# controller_rev3.net
KiCad netlist of a schematic drawn in EAGLE
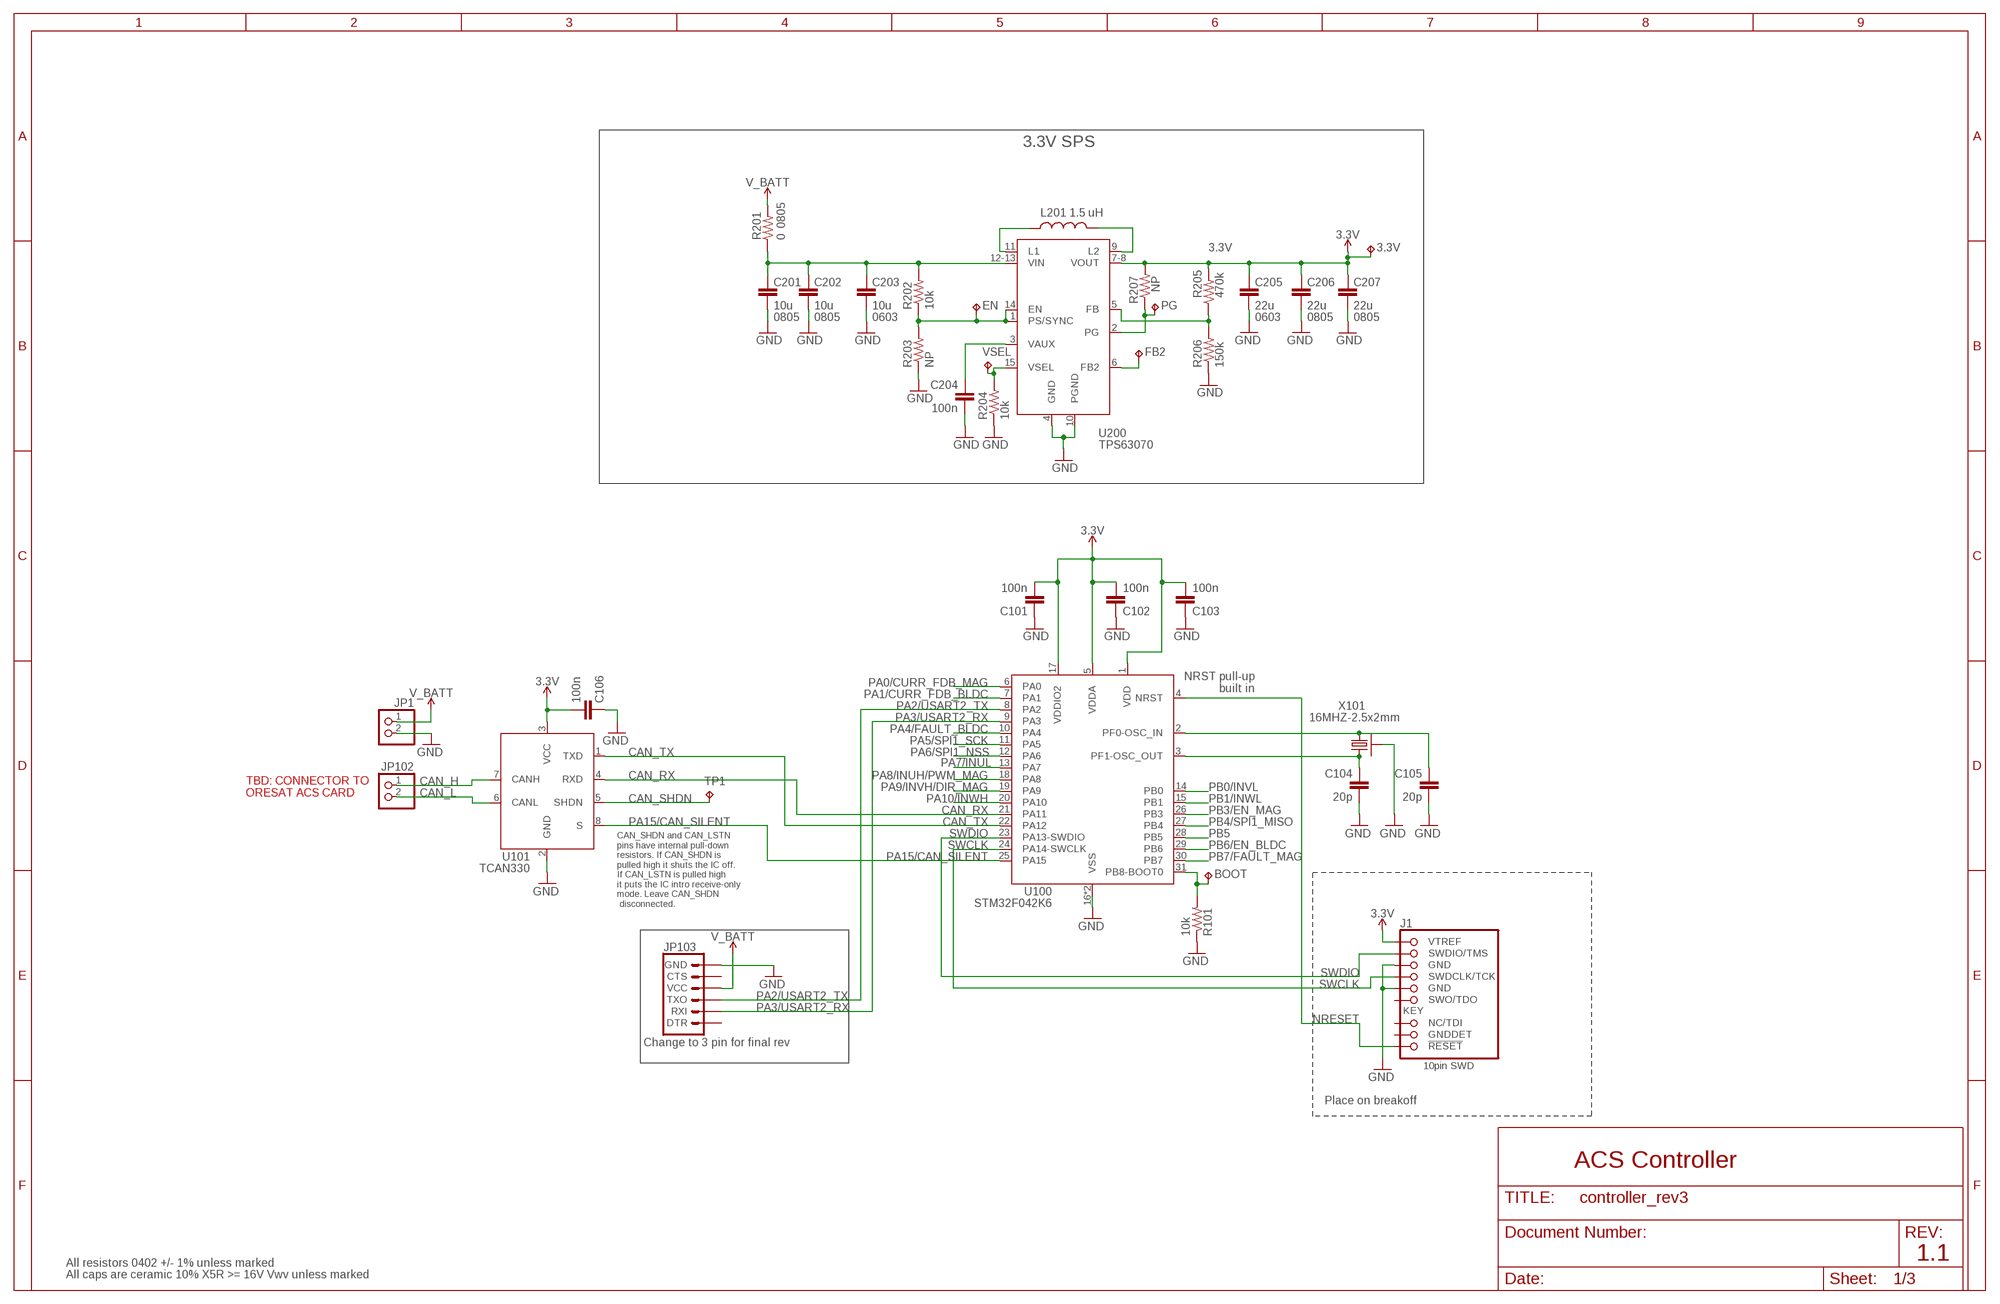
[diagram p0: schematic, sheet 1]
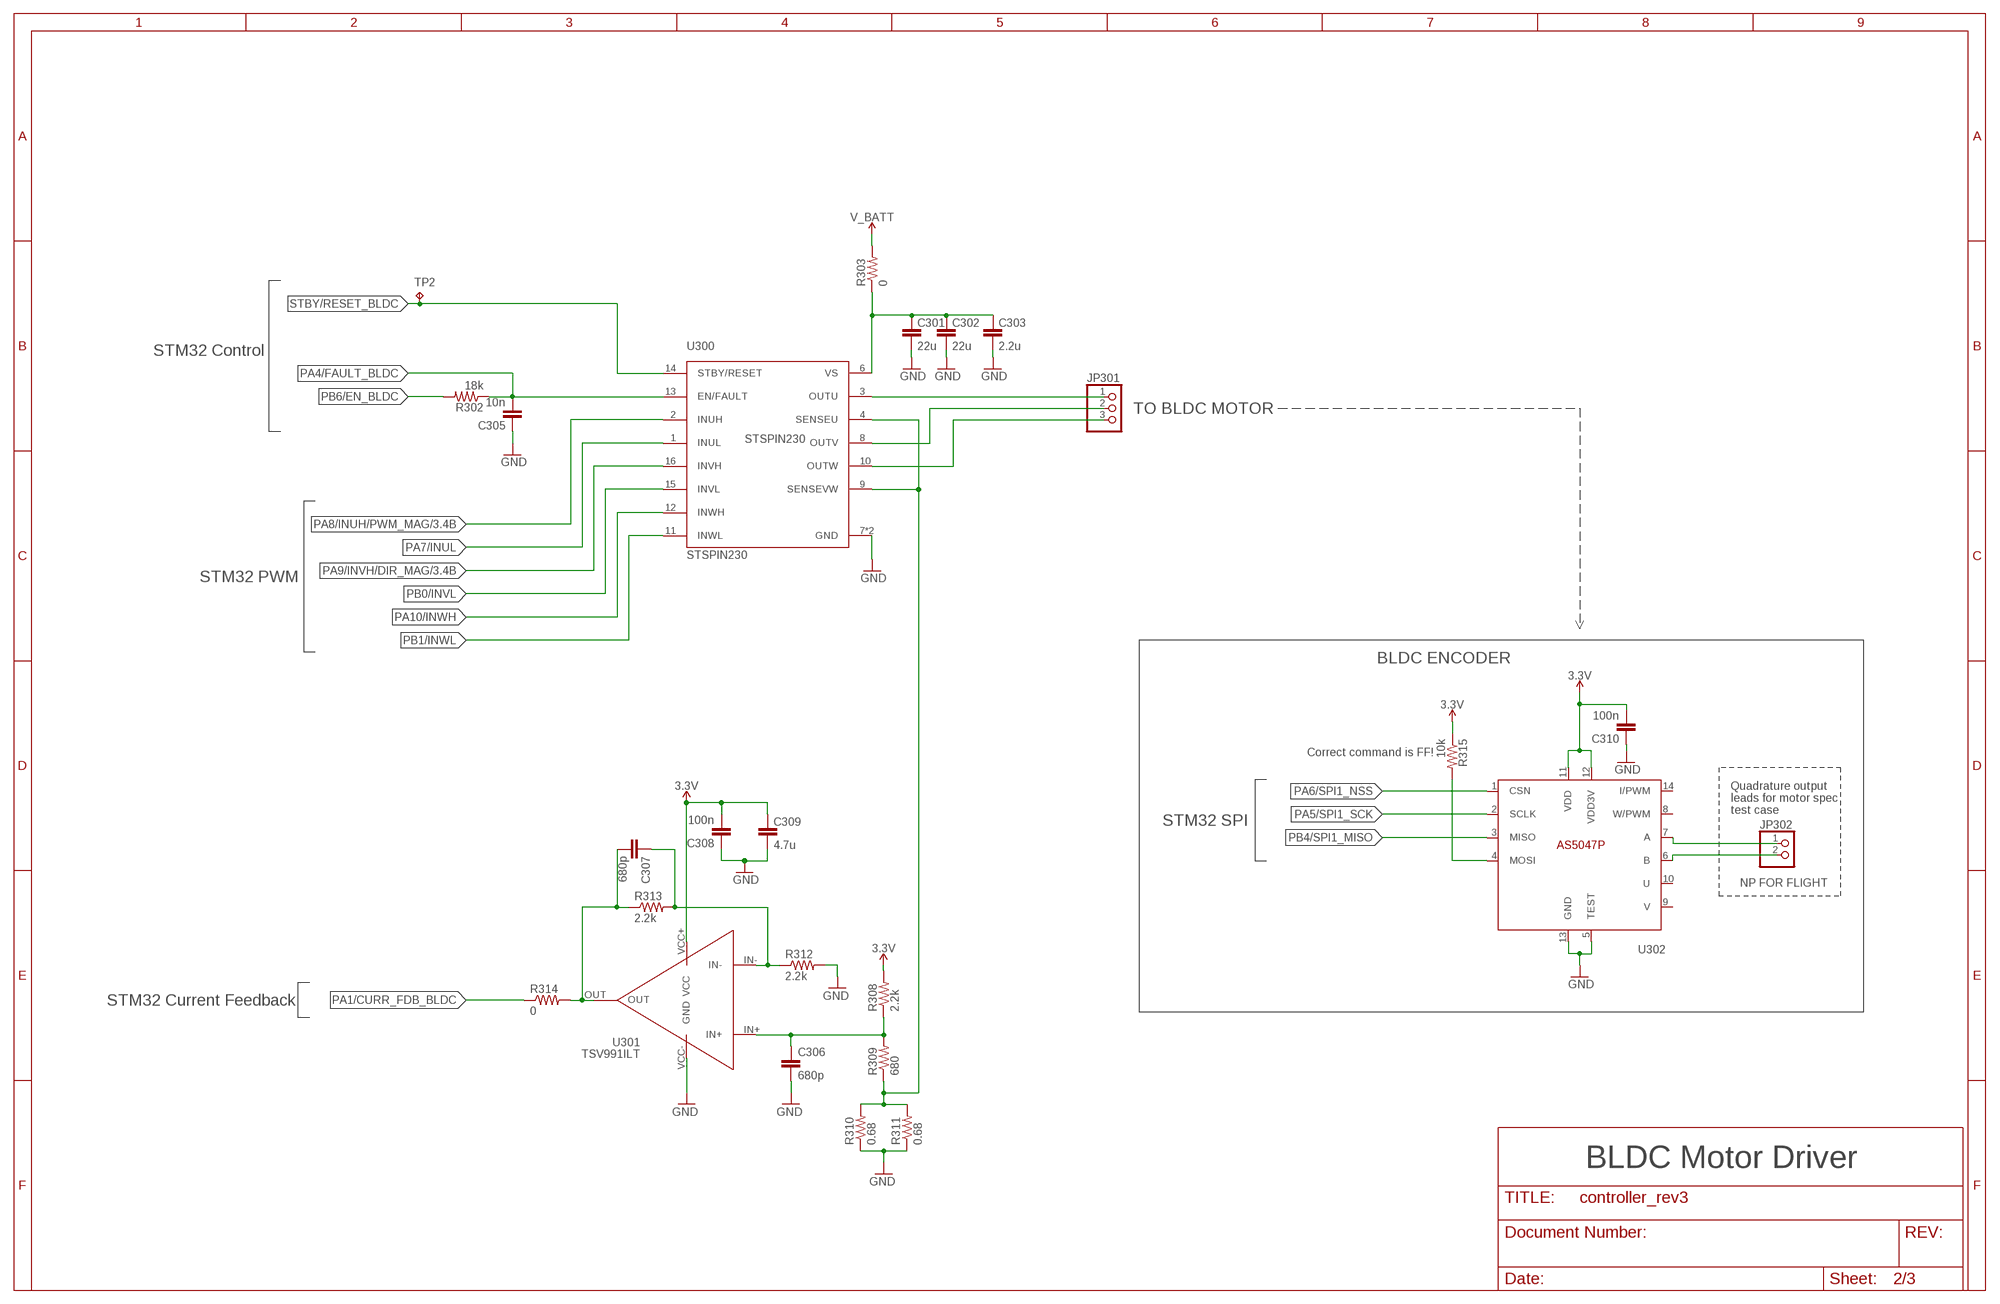
[diagram p1: schematic, sheet 2]
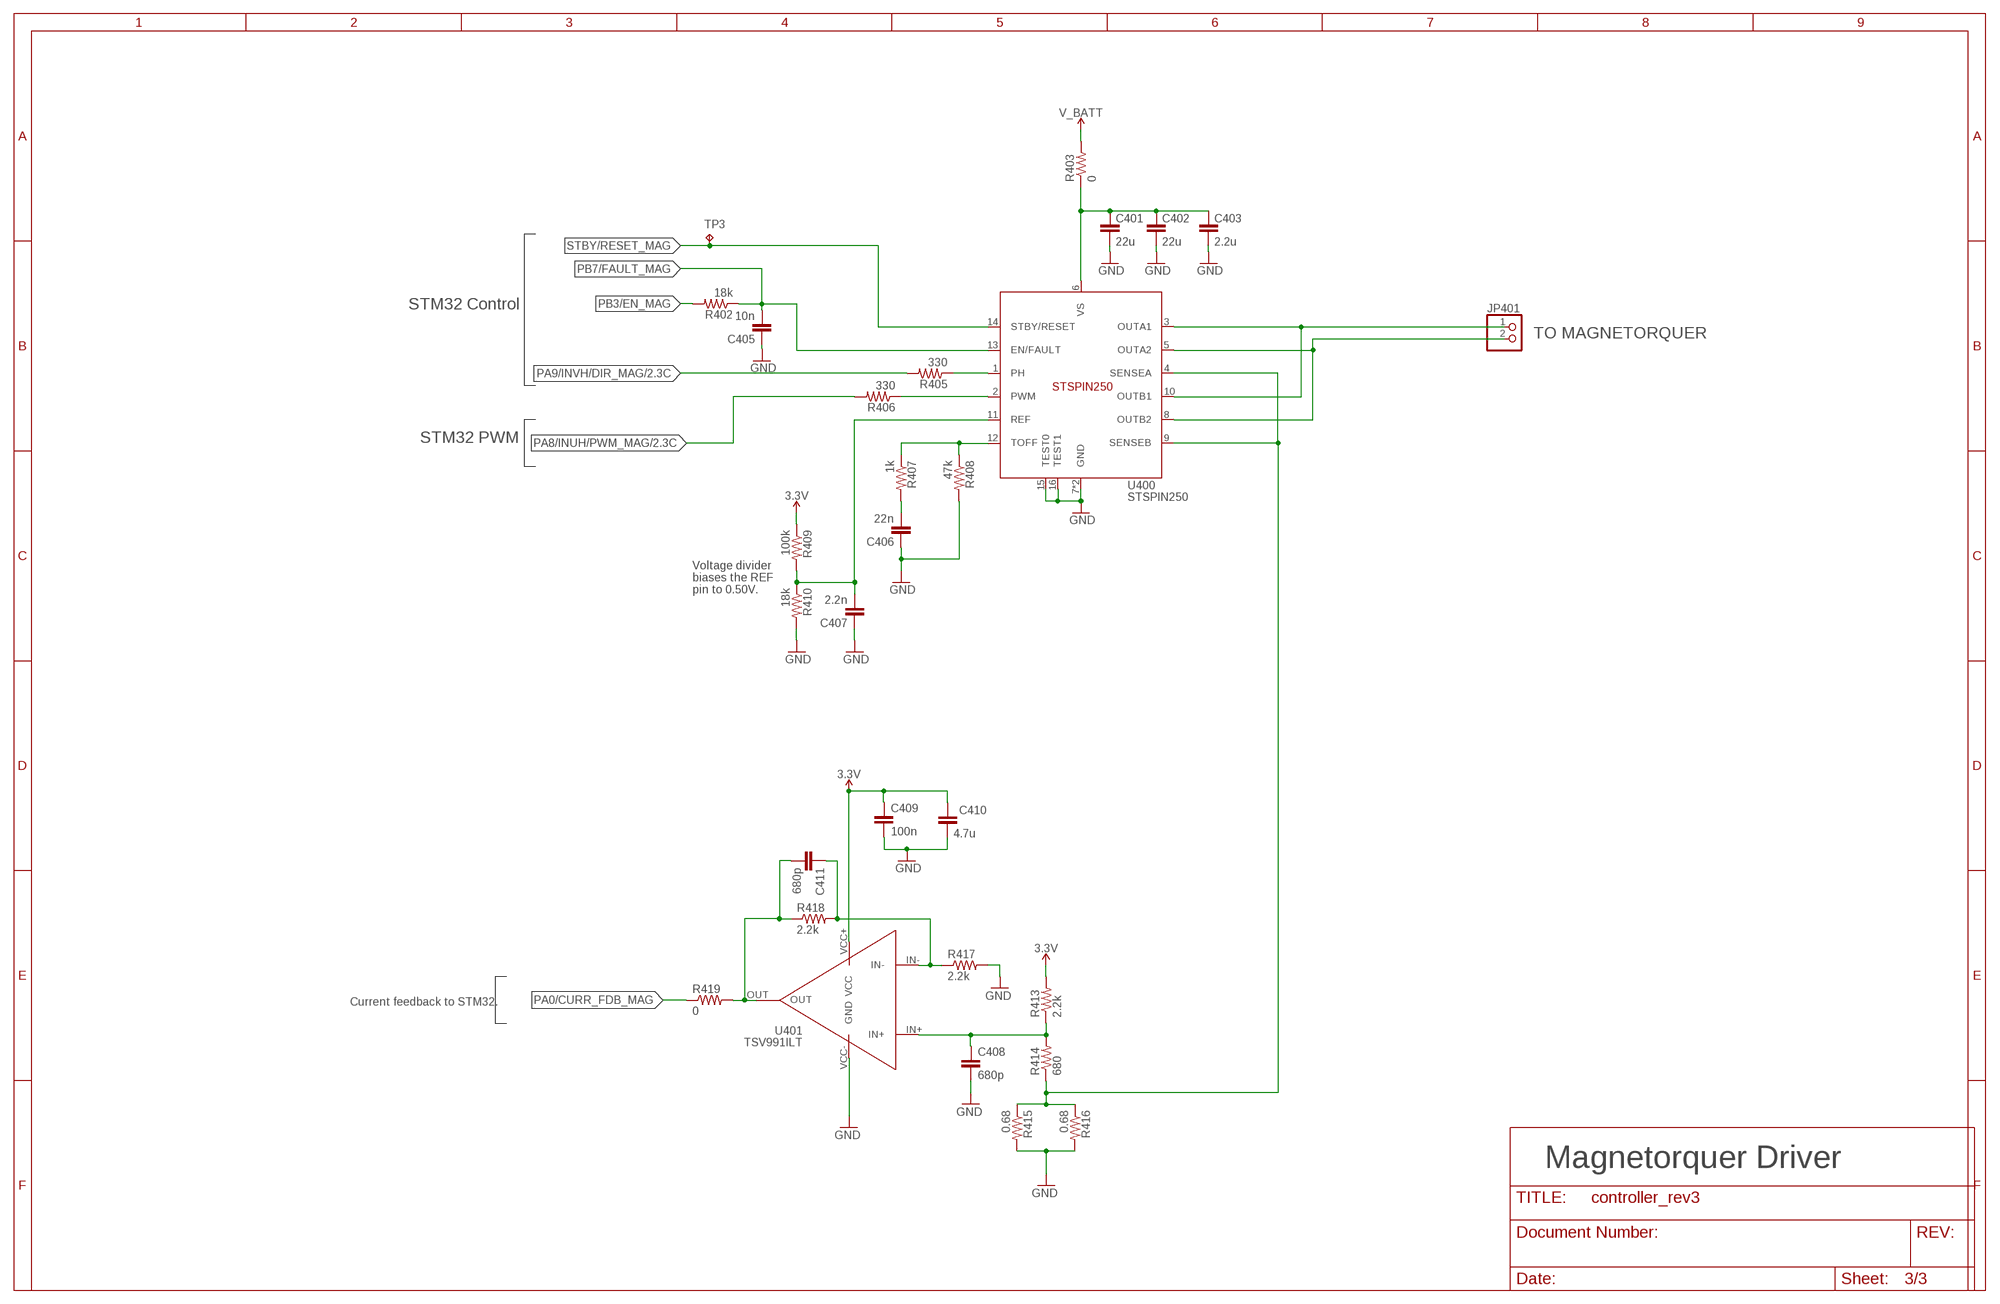
[diagram p2: schematic, sheet 3]

(export (version "E")
  (design (tool "Eeschema 10.0.6"))
  (components
    (comp (ref "3.3V")
      (value "TPTP15SQ")
      (footprint "eagle-import:TP15SQ")
      (libsource (lib "eagle-import") (part "TPTP15SQ"))
    )
    (comp (ref "BOOT")
      (value "TPTP15SQ")
      (footprint "eagle-import:TP15SQ")
      (libsource (lib "eagle-import") (part "TPTP15SQ"))
    )
    (comp (ref "C101")
      (value "100n")
      (footprint "eagle-import:.0402-B-NOSILK")
      (fields (field (name "MFR") "Samsung") (field (name "MPN") "CL05B104KO5NNNC"))
      (libsource (lib "eagle-import") (part "rcl_custom_C-EU0402-B-NOSILK"))
    )
    (comp (ref "C102")
      (value "100n")
      (footprint "eagle-import:.0402-B-NOSILK")
      (fields (field (name "MFR") "Samsung") (field (name "MPN") "CL05B104KO5NNNC"))
      (libsource (lib "eagle-import") (part "rcl_custom_C-EU0402-B-NOSILK"))
    )
    (comp (ref "C103")
      (value "100n")
      (footprint "eagle-import:.0402-B-NOSILK")
      (fields (field (name "MFR") "Samsung") (field (name "MPN") "CL05B104KO5NNNC"))
      (libsource (lib "eagle-import") (part "rcl_custom_C-EU0402-B-NOSILK"))
    )
    (comp (ref "C104")
      (value "20p")
      (footprint "eagle-import:.0402-B-NOSILK")
      (fields (field (name "MFR") "Samsung") (field (name "MPN") "CL05C200JB51PNC"))
      (libsource (lib "eagle-import") (part "rcl_custom_C-EU0402-B-NOSILK"))
    )
    (comp (ref "C105")
      (value "20p")
      (footprint "eagle-import:.0402-B-NOSILK")
      (fields (field (name "MFR") "Samsung") (field (name "MPN") "CL05C200JB51PNC"))
      (libsource (lib "eagle-import") (part "rcl_custom_C-EU0402-B-NOSILK"))
    )
    (comp (ref "C106")
      (value "100n")
      (footprint "eagle-import:.0402-B-NOSILK")
      (fields (field (name "MFR") "Samsung") (field (name "MPN") "CL05B104KO5NNNC"))
      (libsource (lib "eagle-import") (part "rcl_custom_C-EU0402-B-NOSILK"))
    )
    (comp (ref "C201")
      (value "10u")
      (footprint "eagle-import:.0805-B-NOSILK")
      (libsource (lib "eagle-import") (part "C-EU0805-B-NOSILK"))
    )
    (comp (ref "C202")
      (value "10u")
      (footprint "eagle-import:.0805-B-NOSILK")
      (libsource (lib "eagle-import") (part "C-EU0805-B-NOSILK"))
    )
    (comp (ref "C203")
      (value "10u")
      (footprint "eagle-import:.0603-B-NOSILK")
      (fields (field (name "MFR") "Samsung") (field (name "MPN") "CL05B104KO5NNNC"))
      (libsource (lib "eagle-import") (part "C-EU0603-B-NOSILK"))
    )
    (comp (ref "C204")
      (value "100n")
      (footprint "eagle-import:.0402-B-NOSILK")
      (fields (field (name "MFR") "Samsung") (field (name "MPN") "CL05B104KO5NNNC"))
      (libsource (lib "eagle-import") (part "rcl_custom_C-EU0402-B-NOSILK"))
    )
    (comp (ref "C205")
      (value "22u")
      (footprint "eagle-import:.0603-B-NOSILK")
      (fields (field (name "MFR") "Samsung") (field (name "MPN") "CL05B104KO5NNNC"))
      (libsource (lib "eagle-import") (part "C-EU0603-B-NOSILK"))
    )
    (comp (ref "C206")
      (value "22u")
      (footprint "eagle-import:.0805-B-NOSILK")
      (libsource (lib "eagle-import") (part "C-EU0805-B-NOSILK"))
    )
    (comp (ref "C207")
      (value "22u")
      (footprint "eagle-import:.0805-B-NOSILK")
      (libsource (lib "eagle-import") (part "C-EU0805-B-NOSILK"))
    )
    (comp (ref "EN")
      (value "TPTP15SQ")
      (footprint "eagle-import:TP15SQ")
      (libsource (lib "eagle-import") (part "TPTP15SQ"))
    )
    (comp (ref "FB2")
      (value "TPTP15SQ")
      (footprint "eagle-import:TP15SQ")
      (libsource (lib "eagle-import") (part "TPTP15SQ"))
    )
    (comp (ref "J1")
      (value "1.27MM-SWD-CONNECTOR")
      (footprint "eagle-import:1.27MM_2X5")
      (libsource (lib "eagle-import") (part "1.27MM-SWD-CONNECTOR"))
    )
    (comp (ref "JP1")
      (value "PINHD-1X2")
      (footprint "eagle-import:1X02")
      (libsource (lib "eagle-import") (part "PINHD-1X2"))
    )
    (comp (ref "JP102")
      (value "PINHD-1X2")
      (footprint "eagle-import:1X02")
      (libsource (lib "eagle-import") (part "PINHD-1X2"))
    )
    (comp (ref "JP103")
      (value "6_PIN_SERIAL_TARGETSILK")
      (footprint "eagle-import:6_PIN_SERIAL_TARGET_SIDE_W_SILK")
      (libsource (lib "eagle-import") (part "6_PIN_SERIAL_TARGETSILK"))
    )
    (comp (ref "L201")
      (value "1.5 uH")
      (footprint "eagle-import:L-COILCRAFT-XFL4020")
      (fields (field (name "MFR") "Coilcraft") (field (name "MPN") "XFL4020-152ME"))
      (libsource (lib "eagle-import") (part "L-COILCRAFT-XFL4020"))
    )
    (comp (ref "PG")
      (value "TPTP15SQ")
      (footprint "eagle-import:TP15SQ")
      (libsource (lib "eagle-import") (part "TPTP15SQ"))
    )
    (comp (ref "R101")
      (value "10k")
      (footprint "eagle-import:.0402-B-NOSILK")
      (fields (field (name "MFR") "Samsung") (field (name "MPN") "RC1005F6653CS"))
      (libsource (lib "eagle-import") (part "rcl_custom_R-US_0402-B-NOSILK"))
    )
    (comp (ref "R201")
      (value "0")
      (footprint "eagle-import:.0805-B-NOSILK")
      (fields (field (name "MFR") "Rohm") (field (name "MPN") "MCR10EZPJ000"))
      (libsource (lib "eagle-import") (part "rcl_custom_R-US_0805-B-NOSILK"))
    )
    (comp (ref "R202")
      (value "10k")
      (footprint "eagle-import:.0402-B-NOSILK")
      (fields (field (name "MFR") "Samsung") (field (name "MPN") "RC1005F6653CS"))
      (libsource (lib "eagle-import") (part "rcl_custom_R-US_0402-B-NOSILK"))
    )
    (comp (ref "R203")
      (value "NP")
      (footprint "eagle-import:.0402-B-NOSILK")
      (fields (field (name "MFR") "Samsung") (field (name "MPN") "RC1005F6653CS"))
      (libsource (lib "eagle-import") (part "rcl_custom_R-US_0402-B-NOSILK"))
    )
    (comp (ref "R204")
      (value "10k")
      (footprint "eagle-import:.0402-B-NOSILK")
      (fields (field (name "MFR") "Samsung") (field (name "MPN") "RC1005F6653CS"))
      (libsource (lib "eagle-import") (part "rcl_custom_R-US_0402-B-NOSILK"))
    )
    (comp (ref "R205")
      (value "470k")
      (footprint "eagle-import:.0402-B-NOSILK")
      (fields (field (name "MFR") "Samsung") (field (name "MPN") "RC1005F6653CS"))
      (libsource (lib "eagle-import") (part "rcl_custom_R-US_0402-B-NOSILK"))
    )
    (comp (ref "R206")
      (value "150k")
      (footprint "eagle-import:.0402-B-NOSILK")
      (fields (field (name "MFR") "Samsung") (field (name "MPN") "RC1005F6653CS"))
      (libsource (lib "eagle-import") (part "rcl_custom_R-US_0402-B-NOSILK"))
    )
    (comp (ref "R207")
      (value "NP")
      (footprint "eagle-import:.0402-B-NOSILK")
      (fields (field (name "MFR") "Samsung") (field (name "MPN") "RC1005F6653CS"))
      (libsource (lib "eagle-import") (part "rcl_custom_R-US_0402-B-NOSILK"))
    )
    (comp (ref "TP1")
      (value "TPTP06R")
      (footprint "eagle-import:TP06R")
      (libsource (lib "eagle-import") (part "TPTP06R"))
    )
    (comp (ref "U100")
      (value "STM32F042K6")
      (footprint "eagle-import:QFP32-7X7")
      (fields (field (name "MFR") "STMicroelectronics") (field (name "MPN") "STM32F042K6T7"))
      (libsource (lib "eagle-import") (part "STM32F042K6"))
    )
    (comp (ref "U101")
      (value "TCAN330")
      (footprint "eagle-import:SOT23-8_TI-DCN")
      (fields (field (name "MFR") "Texas Instruments") (field (name "MPN") "TCAN330GDCNT"))
      (libsource (lib "eagle-import") (part "TCAN330"))
    )
    (comp (ref "U200")
      (value "TPS63070")
      (footprint "eagle-import:TPS63070X")
      (libsource (lib "eagle-import") (part "TPS63070X"))
    )
    (comp (ref "VSEL")
      (value "TPTP15SQ")
      (footprint "eagle-import:TP15SQ")
      (libsource (lib "eagle-import") (part "TPTP15SQ"))
    )
    (comp (ref "X101")
      (value "16MHZ-2.5x2mm")
      (footprint "eagle-import:CRYSTAL_2.5X2")
      (fields (field (name "MFR") "ECS Inc.") (field (name "MPN") "ECS-160-10-36Q-ES-TR"))
      (libsource (lib "eagle-import") (part "CRYSTAL-WITH-GND"))
    )
    (comp (ref "C301")
      (value "22u")
      (footprint "eagle-import:.0603-B-NOSILK")
      (fields (field (name "MFR") "Samsung") (field (name "MPN") "CL05B104KO5NNNC"))
      (libsource (lib "eagle-import") (part "C-EU0603-B-NOSILK"))
    )
    (comp (ref "C302")
      (value "22u")
      (footprint "eagle-import:.0603-B-NOSILK")
      (fields (field (name "MFR") "Samsung") (field (name "MPN") "CL05B104KO5NNNC"))
      (libsource (lib "eagle-import") (part "C-EU0603-B-NOSILK"))
    )
    (comp (ref "C303")
      (value "2.2u")
      (footprint "eagle-import:.0603-B-NOSILK")
      (fields (field (name "MFR") "Samsung") (field (name "MPN") "CL05B104KO5NNNC"))
      (libsource (lib "eagle-import") (part "C-EU0603-B-NOSILK"))
    )
    (comp (ref "C305")
      (value "10n")
      (footprint "eagle-import:.0402-B-NOSILK")
      (fields (field (name "MFR") "Samsung") (field (name "MPN") "CL05B104KO5NNNC"))
      (libsource (lib "eagle-import") (part "rcl_custom_C-EU0402-B-NOSILK"))
    )
    (comp (ref "C306")
      (value "680p")
      (footprint "eagle-import:.0402-B-NOSILK")
      (fields (field (name "MFR") "Samsung") (field (name "MPN") "CL05B104KO5NNNC"))
      (libsource (lib "eagle-import") (part "rcl_custom_C-EU0402-B-NOSILK"))
    )
    (comp (ref "C307")
      (value "680p")
      (footprint "eagle-import:.0402-B-NOSILK")
      (fields (field (name "MFR") "Samsung") (field (name "MPN") "CL05B104KO5NNNC"))
      (libsource (lib "eagle-import") (part "rcl_custom_C-EU0402-B-NOSILK"))
    )
    (comp (ref "C308")
      (value "100n")
      (footprint "eagle-import:.0402-B-NOSILK")
      (fields (field (name "MFR") "Samsung") (field (name "MPN") "CL05B104KO5NNNC"))
      (libsource (lib "eagle-import") (part "rcl_custom_C-EU0402-B-NOSILK"))
    )
    (comp (ref "C309")
      (value "4.7u")
      (footprint "eagle-import:.0603-B-NOSILK")
      (fields (field (name "MFR") "Samsung") (field (name "MPN") "CL05B104KO5NNNC"))
      (libsource (lib "eagle-import") (part "C-EU0603-B-NOSILK"))
    )
    (comp (ref "C310")
      (value "100n")
      (footprint "eagle-import:.0402-B-NOSILK")
      (fields (field (name "MFR") "Samsung") (field (name "MPN") "CL05B104KO5NNNC"))
      (libsource (lib "eagle-import") (part "rcl_custom_C-EU0402-B-NOSILK"))
    )
    (comp (ref "JP301")
      (value "PINHD-1X03_2.00")
      (footprint "eagle-import:1X03M")
      (libsource (lib "eagle-import") (part "PINHD-1X03_2.00"))
    )
    (comp (ref "JP302")
      (value "PINHD-1X2")
      (footprint "eagle-import:1X02")
      (libsource (lib "eagle-import") (part "PINHD-1X2"))
    )
    (comp (ref "R302")
      (value "18k")
      (footprint "eagle-import:.0402-B-NOSILK")
      (fields (field (name "MFR") "Samsung") (field (name "MPN") "RC1005F6653CS"))
      (libsource (lib "eagle-import") (part "rcl_custom_R-US_0402-B-NOSILK"))
    )
    (comp (ref "R303")
      (value "0")
      (footprint "eagle-import:.0805-B-NOSILK")
      (libsource (lib "eagle-import") (part "R-US_0805-B-NOSILK"))
    )
    (comp (ref "R308")
      (value "2.2k")
      (footprint "eagle-import:.0402-B-NOSILK")
      (fields (field (name "MFR") "Samsung") (field (name "MPN") "RC1005F6653CS"))
      (libsource (lib "eagle-import") (part "rcl_custom_R-US_0402-B-NOSILK"))
    )
    (comp (ref "R309")
      (value "680")
      (footprint "eagle-import:.0402-B-NOSILK")
      (fields (field (name "MFR") "Samsung") (field (name "MPN") "RC1005F6653CS"))
      (libsource (lib "eagle-import") (part "rcl_custom_R-US_0402-B-NOSILK"))
    )
    (comp (ref "R310")
      (value "0.68")
      (footprint "eagle-import:.0805-B-NOSILK")
      (libsource (lib "eagle-import") (part "R-US_0805-B-NOSILK"))
    )
    (comp (ref "R311")
      (value "0.68")
      (footprint "eagle-import:.0805-B-NOSILK")
      (libsource (lib "eagle-import") (part "R-US_0805-B-NOSILK"))
    )
    (comp (ref "R312")
      (value "2.2k")
      (footprint "eagle-import:.0402-B-NOSILK")
      (fields (field (name "MFR") "Samsung") (field (name "MPN") "RC1005F6653CS"))
      (libsource (lib "eagle-import") (part "rcl_custom_R-US_0402-B-NOSILK"))
    )
    (comp (ref "R313")
      (value "2.2k")
      (footprint "eagle-import:.0402-B-NOSILK")
      (fields (field (name "MFR") "Samsung") (field (name "MPN") "RC1005F6653CS"))
      (libsource (lib "eagle-import") (part "rcl_custom_R-US_0402-B-NOSILK"))
    )
    (comp (ref "R314")
      (value "0")
      (footprint "eagle-import:.0402-B-NOSILK")
      (fields (field (name "MFR") "Samsung") (field (name "MPN") "RC1005F6653CS"))
      (libsource (lib "eagle-import") (part "rcl_custom_R-US_0402-B-NOSILK"))
    )
    (comp (ref "R315")
      (value "10k")
      (footprint "eagle-import:.0402-B-NOSILK")
      (fields (field (name "MFR") "Samsung") (field (name "MPN") "RC1005F6653CS"))
      (libsource (lib "eagle-import") (part "rcl_custom_R-US_0402-B-NOSILK"))
    )
    (comp (ref "TP2")
      (value "TPTP06R")
      (footprint "eagle-import:TP06R")
      (libsource (lib "eagle-import") (part "TPTP06R"))
    )
    (comp (ref "U300")
      (value "STSPIN230")
      (footprint "eagle-import:VFQFPN")
      (libsource (lib "eagle-import") (part "STSPIN230"))
    )
    (comp (ref "U301")
      (value "TSV991ILT")
      (footprint "eagle-import:SOT23-5")
      (libsource (lib "eagle-import") (part "TSV991ILT"))
    )
    (comp (ref "U302")
      (value "AS5047P")
      (footprint "eagle-import:TSSOP14")
      (libsource (lib "eagle-import") (part "AS5047P"))
    )
    (comp (ref "C401")
      (value "22u")
      (footprint "eagle-import:.0603-B-NOSILK")
      (fields (field (name "MFR") "Samsung") (field (name "MPN") "CL05B104KO5NNNC"))
      (libsource (lib "eagle-import") (part "C-EU0603-B-NOSILK"))
    )
    (comp (ref "C402")
      (value "22u")
      (footprint "eagle-import:.0603-B-NOSILK")
      (fields (field (name "MFR") "Samsung") (field (name "MPN") "CL05B104KO5NNNC"))
      (libsource (lib "eagle-import") (part "C-EU0603-B-NOSILK"))
    )
    (comp (ref "C403")
      (value "2.2u")
      (footprint "eagle-import:.0603-B-NOSILK")
      (fields (field (name "MFR") "Samsung") (field (name "MPN") "CL05B104KO5NNNC"))
      (libsource (lib "eagle-import") (part "C-EU0603-B-NOSILK"))
    )
    (comp (ref "C405")
      (value "10n")
      (footprint "eagle-import:.0402-B-NOSILK")
      (fields (field (name "MFR") "Samsung") (field (name "MPN") "CL05B104KO5NNNC"))
      (libsource (lib "eagle-import") (part "rcl_custom_C-EU0402-B-NOSILK"))
    )
    (comp (ref "C406")
      (value "22n")
      (footprint "eagle-import:.0402-B-NOSILK")
      (fields (field (name "MFR") "Samsung") (field (name "MPN") "CL05B104KO5NNNC"))
      (libsource (lib "eagle-import") (part "rcl_custom_C-EU0402-B-NOSILK"))
    )
    (comp (ref "C407")
      (value "2.2n")
      (footprint "eagle-import:.0402-B-NOSILK")
      (fields (field (name "MFR") "Samsung") (field (name "MPN") "CL05B104KO5NNNC"))
      (libsource (lib "eagle-import") (part "rcl_custom_C-EU0402-B-NOSILK"))
    )
    (comp (ref "C408")
      (value "680p")
      (footprint "eagle-import:.0402-B-NOSILK")
      (fields (field (name "MFR") "Samsung") (field (name "MPN") "CL05B104KO5NNNC"))
      (libsource (lib "eagle-import") (part "rcl_custom_C-EU0402-B-NOSILK"))
    )
    (comp (ref "C409")
      (value "100n")
      (footprint "eagle-import:.0402-B-NOSILK")
      (fields (field (name "MFR") "Samsung") (field (name "MPN") "CL05B104KO5NNNC"))
      (libsource (lib "eagle-import") (part "rcl_custom_C-EU0402-B-NOSILK"))
    )
    (comp (ref "C410")
      (value "4.7u")
      (footprint "eagle-import:.0603-B-NOSILK")
      (fields (field (name "MFR") "Samsung") (field (name "MPN") "CL05B104KO5NNNC"))
      (libsource (lib "eagle-import") (part "C-EU0603-B-NOSILK"))
    )
    (comp (ref "C411")
      (value "680p")
      (footprint "eagle-import:.0402-B-NOSILK")
      (fields (field (name "MFR") "Samsung") (field (name "MPN") "CL05B104KO5NNNC"))
      (libsource (lib "eagle-import") (part "rcl_custom_C-EU0402-B-NOSILK"))
    )
    (comp (ref "JP401")
      (value "PINHD-1X2")
      (footprint "eagle-import:1X02")
      (libsource (lib "eagle-import") (part "PINHD-1X2"))
    )
    (comp (ref "R402")
      (value "18k")
      (footprint "eagle-import:.0402-B-NOSILK")
      (fields (field (name "MFR") "Samsung") (field (name "MPN") "RC1005F6653CS"))
      (libsource (lib "eagle-import") (part "rcl_custom_R-US_0402-B-NOSILK"))
    )
    (comp (ref "R403")
      (value "0")
      (footprint "eagle-import:.0805-B-NOSILK")
      (libsource (lib "eagle-import") (part "R-US_0805-B-NOSILK"))
    )
    (comp (ref "R405")
      (value "330")
      (footprint "eagle-import:.0402-B-NOSILK")
      (fields (field (name "MFR") "Samsung") (field (name "MPN") "RC1005F6653CS"))
      (libsource (lib "eagle-import") (part "rcl_custom_R-US_0402-B-NOSILK"))
    )
    (comp (ref "R406")
      (value "330")
      (footprint "eagle-import:.0402-B-NOSILK")
      (fields (field (name "MFR") "Samsung") (field (name "MPN") "RC1005F6653CS"))
      (libsource (lib "eagle-import") (part "rcl_custom_R-US_0402-B-NOSILK"))
    )
    (comp (ref "R407")
      (value "1k")
      (footprint "eagle-import:.0402-B-NOSILK")
      (fields (field (name "MFR") "Samsung") (field (name "MPN") "RC1005F6653CS"))
      (libsource (lib "eagle-import") (part "rcl_custom_R-US_0402-B-NOSILK"))
    )
    (comp (ref "R408")
      (value "47k")
      (footprint "eagle-import:.0402-B-NOSILK")
      (fields (field (name "MFR") "Samsung") (field (name "MPN") "RC1005F6653CS"))
      (libsource (lib "eagle-import") (part "rcl_custom_R-US_0402-B-NOSILK"))
    )
    (comp (ref "R409")
      (value "100k")
      (footprint "eagle-import:.0402-B-NOSILK")
      (fields (field (name "MFR") "Samsung") (field (name "MPN") "RC1005F6653CS"))
      (libsource (lib "eagle-import") (part "rcl_custom_R-US_0402-B-NOSILK"))
    )
    (comp (ref "R410")
      (value "18k")
      (footprint "eagle-import:.0402-B-NOSILK")
      (fields (field (name "MFR") "Samsung") (field (name "MPN") "RC1005F6653CS"))
      (libsource (lib "eagle-import") (part "rcl_custom_R-US_0402-B-NOSILK"))
    )
    (comp (ref "R413")
      (value "2.2k")
      (footprint "eagle-import:.0402-B-NOSILK")
      (fields (field (name "MFR") "Samsung") (field (name "MPN") "RC1005F6653CS"))
      (libsource (lib "eagle-import") (part "rcl_custom_R-US_0402-B-NOSILK"))
    )
    (comp (ref "R414")
      (value "680")
      (footprint "eagle-import:.0402-B-NOSILK")
      (fields (field (name "MFR") "Samsung") (field (name "MPN") "RC1005F6653CS"))
      (libsource (lib "eagle-import") (part "rcl_custom_R-US_0402-B-NOSILK"))
    )
    (comp (ref "R415")
      (value "0.68")
      (footprint "eagle-import:.0805-B-NOSILK")
      (libsource (lib "eagle-import") (part "R-US_0805-B-NOSILK"))
    )
    (comp (ref "R416")
      (value "0.68")
      (footprint "eagle-import:.0805-B-NOSILK")
      (libsource (lib "eagle-import") (part "R-US_0805-B-NOSILK"))
    )
    (comp (ref "R417")
      (value "2.2k")
      (footprint "eagle-import:.0402-B-NOSILK")
      (fields (field (name "MFR") "Samsung") (field (name "MPN") "RC1005F6653CS"))
      (libsource (lib "eagle-import") (part "rcl_custom_R-US_0402-B-NOSILK"))
    )
    (comp (ref "R418")
      (value "2.2k")
      (footprint "eagle-import:.0402-B-NOSILK")
      (fields (field (name "MFR") "Samsung") (field (name "MPN") "RC1005F6653CS"))
      (libsource (lib "eagle-import") (part "rcl_custom_R-US_0402-B-NOSILK"))
    )
    (comp (ref "R419")
      (value "0")
      (footprint "eagle-import:.0402-B-NOSILK")
      (fields (field (name "MFR") "Samsung") (field (name "MPN") "RC1005F6653CS"))
      (libsource (lib "eagle-import") (part "rcl_custom_R-US_0402-B-NOSILK"))
    )
    (comp (ref "TP3")
      (value "TPTP06R")
      (footprint "eagle-import:TP06R")
      (libsource (lib "eagle-import") (part "TPTP06R"))
    )
    (comp (ref "U400")
      (value "STSPIN250")
      (footprint "eagle-import:VFQPN")
      (libsource (lib "eagle-import") (part "STSPIN250"))
    )
    (comp (ref "U401")
      (value "TSV991ILT")
      (footprint "eagle-import:SOT23-5")
      (libsource (lib "eagle-import") (part "TSV991ILT"))
    )
  )
  (nets
    (net (code "1") (name "3.3V") (class "Default")
      (node (ref "3.3V") (pin "TP") (pinfunction "TP_TP") (pintype "input"))
      (node (ref "C101") (pin "2") (pinfunction "2_2") (pintype "passive"))
      (node (ref "C102") (pin "2") (pinfunction "2_2") (pintype "passive"))
      (node (ref "C103") (pin "2") (pinfunction "2_2") (pintype "passive"))
      (node (ref "C106") (pin "2") (pinfunction "2_2") (pintype "passive"))
      (node (ref "C205") (pin "1") (pinfunction "1_1") (pintype "passive"))
      (node (ref "C206") (pin "1") (pinfunction "1_1") (pintype "passive"))
      (node (ref "C207") (pin "1") (pinfunction "1_1") (pintype "passive"))
      (node (ref "C308") (pin "2") (pinfunction "2_2") (pintype "passive"))
      (node (ref "C309") (pin "1") (pinfunction "1_1") (pintype "passive"))
      (node (ref "C310") (pin "2") (pinfunction "2_2") (pintype "passive"))
      (node (ref "C409") (pin "1") (pinfunction "1_1") (pintype "passive"))
      (node (ref "C410") (pin "1") (pinfunction "1_1") (pintype "passive"))
      (node (ref "J1") (pin "VTREF") (pinfunction "VTREF_VTREF") (pintype "passive"))
      (node (ref "R205") (pin "2") (pinfunction "2_2") (pintype "passive"))
      (node (ref "R207") (pin "2") (pinfunction "2_2") (pintype "passive"))
      (node (ref "R308") (pin "2") (pinfunction "2_2") (pintype "passive"))
      (node (ref "R315") (pin "1") (pinfunction "1_1") (pintype "passive"))
      (node (ref "R409") (pin "1") (pinfunction "1_1") (pintype "passive"))
      (node (ref "R413") (pin "2") (pinfunction "2_2") (pintype "passive"))
      (node (ref "U100") (pin "1") (pinfunction "VDD_1") (pintype "power_in"))
      (node (ref "U100") (pin "17") (pinfunction "VDDIO2_17") (pintype "power_in"))
      (node (ref "U100") (pin "5") (pinfunction "VDDA_5") (pintype "power_in"))
      (node (ref "U101") (pin "3") (pinfunction "VCC_3") (pintype "power_in"))
      (node (ref "U200") (pin "7-8") (pinfunction "VOUT_7-8") (pintype "power_in"))
      (node (ref "U301") (pin "VCC+") (pinfunction "VCC_VCC+") (pintype "bidirectional"))
      (node (ref "U302") (pin "11") (pinfunction "VDD_11") (pintype "power_in"))
      (node (ref "U302") (pin "12") (pinfunction "VDD3V_12") (pintype "power_in"))
      (node (ref "U401") (pin "VCC+") (pinfunction "VCC_VCC+") (pintype "bidirectional"))
    )
    (net (code "2") (name "CAN_H") (class "Default")
      (node (ref "JP102") (pin "1") (pinfunction "1_1") (pintype "passive"))
      (node (ref "U101") (pin "7") (pinfunction "CANH_7") (pintype "bidirectional"))
    )
    (net (code "3") (name "CAN_L") (class "Default")
      (node (ref "JP102") (pin "2") (pinfunction "2_2") (pintype "passive"))
      (node (ref "U101") (pin "6") (pinfunction "CANL_6") (pintype "bidirectional"))
    )
    (net (code "4") (name "CAN_RX") (class "Default")
      (node (ref "U100") (pin "21") (pinfunction "PA11_21") (pintype "bidirectional"))
      (node (ref "U101") (pin "4") (pinfunction "RXD_4") (pintype "output"))
    )
    (net (code "5") (name "CAN_SHDN") (class "Default")
      (node (ref "TP1") (pin "TP") (pinfunction "TP_TP") (pintype "input"))
      (node (ref "U101") (pin "5") (pinfunction "SHDN_5") (pintype "input"))
    )
    (net (code "6") (name "CAN_TX") (class "Default")
      (node (ref "U100") (pin "22") (pinfunction "PA12_22") (pintype "bidirectional"))
      (node (ref "U101") (pin "1") (pinfunction "TXD_1") (pintype "input"))
    )
    (net (code "7") (name "GND") (class "Default")
      (node (ref "C101") (pin "1") (pinfunction "1_1") (pintype "passive"))
      (node (ref "C102") (pin "1") (pinfunction "1_1") (pintype "passive"))
      (node (ref "C103") (pin "1") (pinfunction "1_1") (pintype "passive"))
      (node (ref "C104") (pin "2") (pinfunction "2_2") (pintype "passive"))
      (node (ref "C105") (pin "2") (pinfunction "2_2") (pintype "passive"))
      (node (ref "C106") (pin "1") (pinfunction "1_1") (pintype "passive"))
      (node (ref "C201") (pin "2") (pinfunction "2_2") (pintype "passive"))
      (node (ref "C202") (pin "2") (pinfunction "2_2") (pintype "passive"))
      (node (ref "C203") (pin "2") (pinfunction "2_2") (pintype "passive"))
      (node (ref "C204") (pin "2") (pinfunction "2_2") (pintype "passive"))
      (node (ref "C205") (pin "2") (pinfunction "2_2") (pintype "passive"))
      (node (ref "C206") (pin "2") (pinfunction "2_2") (pintype "passive"))
      (node (ref "C207") (pin "2") (pinfunction "2_2") (pintype "passive"))
      (node (ref "C301") (pin "2") (pinfunction "2_2") (pintype "passive"))
      (node (ref "C302") (pin "2") (pinfunction "2_2") (pintype "passive"))
      (node (ref "C303") (pin "2") (pinfunction "2_2") (pintype "passive"))
      (node (ref "C305") (pin "1") (pinfunction "1_1") (pintype "passive"))
      (node (ref "C306") (pin "2") (pinfunction "2_2") (pintype "passive"))
      (node (ref "C308") (pin "1") (pinfunction "1_1") (pintype "passive"))
      (node (ref "C309") (pin "2") (pinfunction "2_2") (pintype "passive"))
      (node (ref "C310") (pin "1") (pinfunction "1_1") (pintype "passive"))
      (node (ref "C401") (pin "2") (pinfunction "2_2") (pintype "passive"))
      (node (ref "C402") (pin "2") (pinfunction "2_2") (pintype "passive"))
      (node (ref "C403") (pin "2") (pinfunction "2_2") (pintype "passive"))
      (node (ref "C405") (pin "1") (pinfunction "1_1") (pintype "passive"))
      (node (ref "C406") (pin "1") (pinfunction "1_1") (pintype "passive"))
      (node (ref "C407") (pin "1") (pinfunction "1_1") (pintype "passive"))
      (node (ref "C408") (pin "2") (pinfunction "2_2") (pintype "passive"))
      (node (ref "C409") (pin "2") (pinfunction "2_2") (pintype "passive"))
      (node (ref "C410") (pin "2") (pinfunction "2_2") (pintype "passive"))
      (node (ref "J1") (pin "GND") (pinfunction "GND_GND") (pintype "passive"))
      (node (ref "J1") (pin "GND@2") (pinfunction "GND_GND@2") (pintype "passive"))
      (node (ref "JP1") (pin "2") (pinfunction "2_2") (pintype "passive"))
      (node (ref "JP103") (pin "P$6") (pinfunction "GND_P$6") (pintype "passive"))
      (node (ref "R101") (pin "1") (pinfunction "1_1") (pintype "passive"))
      (node (ref "R203") (pin "1") (pinfunction "1_1") (pintype "passive"))
      (node (ref "R204") (pin "1") (pinfunction "1_1") (pintype "passive"))
      (node (ref "R206") (pin "1") (pinfunction "1_1") (pintype "passive"))
      (node (ref "R310") (pin "1") (pinfunction "1_1") (pintype "passive"))
      (node (ref "R311") (pin "1") (pinfunction "1_1") (pintype "passive"))
      (node (ref "R312") (pin "2") (pinfunction "2_2") (pintype "passive"))
      (node (ref "R408") (pin "2") (pinfunction "2_2") (pintype "passive"))
      (node (ref "R410") (pin "2") (pinfunction "2_2") (pintype "passive"))
      (node (ref "R415") (pin "2") (pinfunction "2_2") (pintype "passive"))
      (node (ref "R416") (pin "2") (pinfunction "2_2") (pintype "passive"))
      (node (ref "R417") (pin "2") (pinfunction "2_2") (pintype "passive"))
      (node (ref "U100") (pin "16") (pinfunction "VSS_16") (pintype "power_in"))
      (node (ref "U100") (pin "32") (pinfunction "VSS_32") (pintype "power_in"))
      (node (ref "U101") (pin "2") (pinfunction "GND_2") (pintype "power_in"))
      (node (ref "U200") (pin "10") (pinfunction "PGND_10") (pintype "power_in"))
      (node (ref "U200") (pin "4") (pinfunction "GND_4") (pintype "power_in"))
      (node (ref "U300") (pin "7") (pinfunction "GND_7") (pintype "power_in"))
      (node (ref "U300") (pin "EPAD") (pinfunction "GND_EPAD") (pintype "power_in"))
      (node (ref "U301") (pin "VCC-") (pinfunction "GND_VCC-") (pintype "bidirectional"))
      (node (ref "U302") (pin "13") (pinfunction "GND_13") (pintype "power_in"))
      (node (ref "U302") (pin "5") (pinfunction "TEST_5") (pintype "power_in"))
      (node (ref "U400") (pin "15") (pinfunction "TEST0_15") (pintype "bidirectional"))
      (node (ref "U400") (pin "16") (pinfunction "TEST1_16") (pintype "bidirectional"))
      (node (ref "U400") (pin "7") (pinfunction "GND_7") (pintype "power_in"))
      (node (ref "U400") (pin "EPAD") (pinfunction "GND_EPAD") (pintype "power_in"))
      (node (ref "U401") (pin "VCC-") (pinfunction "GND_VCC-") (pintype "bidirectional"))
      (node (ref "X101") (pin "2") (pinfunction "SHIELD_2") (pintype "power_in"))
      (node (ref "X101") (pin "4") (pinfunction "SHIELD_4") (pintype "power_in"))
    )
    (net (code "8") (name "NRESET") (class "Default")
      (node (ref "J1") (pin "!RESET") (pinfunction "~{RESET}_!RESET") (pintype "passive"))
      (node (ref "U100") (pin "4") (pinfunction "NRST_4") (pintype "bidirectional"))
    )
    (net (code "9") (name "Net-(C306-Pad1)") (class "Default")
      (node (ref "C306") (pin "1") (pinfunction "1_1") (pintype "passive"))
      (node (ref "R308") (pin "1") (pinfunction "1_1") (pintype "passive"))
      (node (ref "R309") (pin "2") (pinfunction "2_2") (pintype "passive"))
      (node (ref "U301") (pin "IN+") (pinfunction "IN+_IN+") (pintype "bidirectional"))
    )
    (net (code "10") (name "Net-(C307-Pad1)") (class "Default")
      (node (ref "C307") (pin "1") (pinfunction "1_1") (pintype "passive"))
      (node (ref "R312") (pin "1") (pinfunction "1_1") (pintype "passive"))
      (node (ref "R313") (pin "2") (pinfunction "2_2") (pintype "passive"))
      (node (ref "U301") (pin "IN-") (pinfunction "IN-_IN-") (pintype "bidirectional"))
    )
    (net (code "11") (name "Net-(C307-Pad2)") (class "Default")
      (node (ref "C307") (pin "2") (pinfunction "2_2") (pintype "passive"))
      (node (ref "R313") (pin "1") (pinfunction "1_1") (pintype "passive"))
      (node (ref "R314") (pin "2") (pinfunction "2_2") (pintype "passive"))
      (node (ref "U301") (pin "OUT") (pinfunction "OUT_OUT") (pintype "bidirectional"))
    )
    (net (code "12") (name "Net-(C406-Pad2)") (class "Default")
      (node (ref "C406") (pin "2") (pinfunction "2_2") (pintype "passive"))
      (node (ref "R407") (pin "2") (pinfunction "2_2") (pintype "passive"))
    )
    (net (code "13") (name "Net-(C408-Pad1)") (class "Default")
      (node (ref "C408") (pin "1") (pinfunction "1_1") (pintype "passive"))
      (node (ref "R413") (pin "1") (pinfunction "1_1") (pintype "passive"))
      (node (ref "R414") (pin "2") (pinfunction "2_2") (pintype "passive"))
      (node (ref "U401") (pin "IN+") (pinfunction "IN+_IN+") (pintype "bidirectional"))
    )
    (net (code "14") (name "Net-(C411-Pad1)") (class "Default")
      (node (ref "C411") (pin "1") (pinfunction "1_1") (pintype "passive"))
      (node (ref "R417") (pin "1") (pinfunction "1_1") (pintype "passive"))
      (node (ref "R418") (pin "2") (pinfunction "2_2") (pintype "passive"))
      (node (ref "U401") (pin "IN-") (pinfunction "IN-_IN-") (pintype "bidirectional"))
    )
    (net (code "15") (name "Net-(C411-Pad2)") (class "Default")
      (node (ref "C411") (pin "2") (pinfunction "2_2") (pintype "passive"))
      (node (ref "R418") (pin "1") (pinfunction "1_1") (pintype "passive"))
      (node (ref "R419") (pin "2") (pinfunction "2_2") (pintype "passive"))
      (node (ref "U401") (pin "OUT") (pinfunction "OUT_OUT") (pintype "bidirectional"))
    )
    (net (code "16") (name "Net-(U100-PB8-BOOT0)") (class "Default")
      (node (ref "BOOT") (pin "TP") (pinfunction "TP_TP") (pintype "input"))
      (node (ref "R101") (pin "2") (pinfunction "2_2") (pintype "passive"))
      (node (ref "U100") (pin "31") (pinfunction "PB8-BOOT0_31") (pintype "bidirectional"))
    )
    (net (code "17") (name "Net-(U100-PF0-OSC_IN)") (class "Default")
      (node (ref "C105") (pin "1") (pinfunction "1_1") (pintype "passive"))
      (node (ref "U100") (pin "2") (pinfunction "PF0-OSC_IN_2") (pintype "bidirectional"))
      (node (ref "X101") (pin "1") (pinfunction "1_1") (pintype "passive"))
    )
    (net (code "18") (name "Net-(U100-PF1-OSC_OUT)") (class "Default")
      (node (ref "C104") (pin "1") (pinfunction "1_1") (pintype "passive"))
      (node (ref "U100") (pin "3") (pinfunction "PF1-OSC_OUT_3") (pintype "bidirectional"))
      (node (ref "X101") (pin "3") (pinfunction "2_3") (pintype "passive"))
    )
    (net (code "19") (name "Net-(U200-EN)") (class "Default")
      (node (ref "EN") (pin "TP") (pinfunction "TP_TP") (pintype "input"))
      (node (ref "R202") (pin "1") (pinfunction "1_1") (pintype "passive"))
      (node (ref "R203") (pin "2") (pinfunction "2_2") (pintype "passive"))
      (node (ref "U200") (pin "1") (pinfunction "PS/SYNC_1") (pintype "input"))
      (node (ref "U200") (pin "14") (pinfunction "EN_14") (pintype "input"))
    )
    (net (code "20") (name "Net-(U200-FB)") (class "Default")
      (node (ref "R205") (pin "1") (pinfunction "1_1") (pintype "passive"))
      (node (ref "R206") (pin "2") (pinfunction "2_2") (pintype "passive"))
      (node (ref "U200") (pin "5") (pinfunction "FB_5") (pintype "passive"))
    )
    (net (code "21") (name "Net-(U200-FB2)") (class "Default")
      (node (ref "FB2") (pin "TP") (pinfunction "TP_TP") (pintype "input"))
      (node (ref "U200") (pin "6") (pinfunction "FB2_6") (pintype "passive"))
    )
    (net (code "22") (name "Net-(U200-L1)") (class "Default")
      (node (ref "L201") (pin "1") (pinfunction "1_1") (pintype "passive"))
      (node (ref "U200") (pin "11") (pinfunction "L1_11") (pintype "passive"))
    )
    (net (code "23") (name "Net-(U200-L2)") (class "Default")
      (node (ref "L201") (pin "2") (pinfunction "2_2") (pintype "passive"))
      (node (ref "U200") (pin "9") (pinfunction "L2_9") (pintype "passive"))
    )
    (net (code "24") (name "Net-(U200-PG)") (class "Default")
      (node (ref "PG") (pin "TP") (pinfunction "TP_TP") (pintype "input"))
      (node (ref "R207") (pin "1") (pinfunction "1_1") (pintype "passive"))
      (node (ref "U200") (pin "2") (pinfunction "PG_2") (pintype "open_collector"))
    )
    (net (code "25") (name "Net-(U200-VAUX)") (class "Default")
      (node (ref "C204") (pin "1") (pinfunction "1_1") (pintype "passive"))
      (node (ref "U200") (pin "3") (pinfunction "VAUX_3") (pintype "output"))
    )
    (net (code "26") (name "Net-(U200-VIN)") (class "Default")
      (node (ref "C201") (pin "1") (pinfunction "1_1") (pintype "passive"))
      (node (ref "C202") (pin "1") (pinfunction "1_1") (pintype "passive"))
      (node (ref "C203") (pin "1") (pinfunction "1_1") (pintype "passive"))
      (node (ref "R201") (pin "1") (pinfunction "1_1") (pintype "passive"))
      (node (ref "R202") (pin "2") (pinfunction "2_2") (pintype "passive"))
      (node (ref "U200") (pin "12-13") (pinfunction "VIN_12-13") (pintype "power_in"))
    )
    (net (code "27") (name "Net-(U200-VSEL)") (class "Default")
      (node (ref "R204") (pin "2") (pinfunction "2_2") (pintype "passive"))
      (node (ref "U200") (pin "15") (pinfunction "VSEL_15") (pintype "input"))
      (node (ref "VSEL") (pin "TP") (pinfunction "TP_TP") (pintype "input"))
    )
    (net (code "28") (name "Net-(U300-OUTU)") (class "Default")
      (node (ref "JP301") (pin "1") (pinfunction "1_1") (pintype "passive"))
      (node (ref "U300") (pin "3") (pinfunction "OUTU_3") (pintype "output"))
    )
    (net (code "29") (name "Net-(U300-OUTV)") (class "Default")
      (node (ref "JP301") (pin "2") (pinfunction "2_2") (pintype "passive"))
      (node (ref "U300") (pin "8") (pinfunction "OUTV_8") (pintype "output"))
    )
    (net (code "30") (name "Net-(U300-OUTW)") (class "Default")
      (node (ref "JP301") (pin "3") (pinfunction "3_3") (pintype "passive"))
      (node (ref "U300") (pin "10") (pinfunction "OUTW_10") (pintype "output"))
    )
    (net (code "31") (name "Net-(U300-SENSEU)") (class "Default")
      (node (ref "R309") (pin "1") (pinfunction "1_1") (pintype "passive"))
      (node (ref "R310") (pin "2") (pinfunction "2_2") (pintype "passive"))
      (node (ref "R311") (pin "2") (pinfunction "2_2") (pintype "passive"))
      (node (ref "U300") (pin "4") (pinfunction "SENSEU_4") (pintype "output"))
      (node (ref "U300") (pin "9") (pinfunction "SENSEVW_9") (pintype "output"))
    )
    (net (code "32") (name "Net-(U300-VS)") (class "Default")
      (node (ref "C301") (pin "1") (pinfunction "1_1") (pintype "passive"))
      (node (ref "C302") (pin "1") (pinfunction "1_1") (pintype "passive"))
      (node (ref "C303") (pin "1") (pinfunction "1_1") (pintype "passive"))
      (node (ref "R303") (pin "1") (pinfunction "1_1") (pintype "passive"))
      (node (ref "U300") (pin "6") (pinfunction "VS_6") (pintype "power_in"))
    )
    (net (code "33") (name "Net-(U302-A)") (class "Default")
      (node (ref "JP302") (pin "1") (pinfunction "1_1") (pintype "passive"))
      (node (ref "U302") (pin "7") (pinfunction "A_7") (pintype "output"))
    )
    (net (code "34") (name "Net-(U302-B)") (class "Default")
      (node (ref "JP302") (pin "2") (pinfunction "2_2") (pintype "passive"))
      (node (ref "U302") (pin "6") (pinfunction "B_6") (pintype "output"))
    )
    (net (code "35") (name "Net-(U302-MOSI)") (class "Default")
      (node (ref "R315") (pin "2") (pinfunction "2_2") (pintype "passive"))
      (node (ref "U302") (pin "4") (pinfunction "MOSI_4") (pintype "input"))
    )
    (net (code "36") (name "Net-(U400-OUTA1)") (class "Default")
      (node (ref "JP401") (pin "1") (pinfunction "1_1") (pintype "passive"))
      (node (ref "U400") (pin "10") (pinfunction "OUTB1_10") (pintype "output"))
      (node (ref "U400") (pin "3") (pinfunction "OUTA1_3") (pintype "output"))
    )
    (net (code "37") (name "Net-(U400-OUTA2)") (class "Default")
      (node (ref "JP401") (pin "2") (pinfunction "2_2") (pintype "passive"))
      (node (ref "U400") (pin "5") (pinfunction "OUTA2_5") (pintype "output"))
      (node (ref "U400") (pin "8") (pinfunction "OUTB2_8") (pintype "output"))
    )
    (net (code "38") (name "Net-(U400-PH)") (class "Default")
      (node (ref "R405") (pin "1") (pinfunction "1_1") (pintype "passive"))
      (node (ref "U400") (pin "1") (pinfunction "PH_1") (pintype "input"))
    )
    (net (code "39") (name "Net-(U400-PWM)") (class "Default")
      (node (ref "R406") (pin "1") (pinfunction "1_1") (pintype "passive"))
      (node (ref "U400") (pin "2") (pinfunction "PWM_2") (pintype "input"))
    )
    (net (code "40") (name "Net-(U400-REF)") (class "Default")
      (node (ref "C407") (pin "2") (pinfunction "2_2") (pintype "passive"))
      (node (ref "R409") (pin "2") (pinfunction "2_2") (pintype "passive"))
      (node (ref "R410") (pin "1") (pinfunction "1_1") (pintype "passive"))
      (node (ref "U400") (pin "11") (pinfunction "REF_11") (pintype "passive"))
    )
    (net (code "41") (name "Net-(U400-SENSEA)") (class "Default")
      (node (ref "R414") (pin "1") (pinfunction "1_1") (pintype "passive"))
      (node (ref "R415") (pin "1") (pinfunction "1_1") (pintype "passive"))
      (node (ref "R416") (pin "1") (pinfunction "1_1") (pintype "passive"))
      (node (ref "U400") (pin "4") (pinfunction "SENSEA_4") (pintype "output"))
      (node (ref "U400") (pin "9") (pinfunction "SENSEB_9") (pintype "output"))
    )
    (net (code "42") (name "Net-(U400-TOFF)") (class "Default")
      (node (ref "R407") (pin "1") (pinfunction "1_1") (pintype "passive"))
      (node (ref "R408") (pin "1") (pinfunction "1_1") (pintype "passive"))
      (node (ref "U400") (pin "12") (pinfunction "TOFF_12") (pintype "passive"))
    )
    (net (code "43") (name "Net-(U400-VS)") (class "Default")
      (node (ref "C401") (pin "1") (pinfunction "1_1") (pintype "passive"))
      (node (ref "C402") (pin "1") (pinfunction "1_1") (pintype "passive"))
      (node (ref "C403") (pin "1") (pinfunction "1_1") (pintype "passive"))
      (node (ref "R403") (pin "1") (pinfunction "1_1") (pintype "passive"))
      (node (ref "U400") (pin "6") (pinfunction "VS_6") (pintype "power_in"))
    )
    (net (code "44") (name "PA0{slash}CURR_FDB_MAG") (class "Default")
      (node (ref "R419") (pin "1") (pinfunction "1_1") (pintype "passive"))
      (node (ref "U100") (pin "6") (pinfunction "PA0_6") (pintype "bidirectional"))
    )
    (net (code "45") (name "PA1{slash}CURR_FDB_BLDC") (class "Default")
      (node (ref "R314") (pin "1") (pinfunction "1_1") (pintype "passive"))
      (node (ref "U100") (pin "7") (pinfunction "PA1_7") (pintype "bidirectional"))
    )
    (net (code "46") (name "PA2{slash}USART2_TX") (class "Default")
      (node (ref "JP103") (pin "P$2") (pinfunction "TXO_P$2") (pintype "passive"))
      (node (ref "U100") (pin "8") (pinfunction "PA2_8") (pintype "bidirectional"))
    )
    (net (code "47") (name "PA3{slash}USART2_RX") (class "Default")
      (node (ref "JP103") (pin "P$3") (pinfunction "RXI_P$3") (pintype "passive"))
      (node (ref "U100") (pin "9") (pinfunction "PA3_9") (pintype "bidirectional"))
    )
    (net (code "48") (name "PA4{slash}FAULT_BLDC") (class "Default")
      (node (ref "C305") (pin "2") (pinfunction "2_2") (pintype "passive"))
      (node (ref "R302") (pin "1") (pinfunction "1_1") (pintype "passive"))
      (node (ref "U100") (pin "10") (pinfunction "PA4_10") (pintype "bidirectional"))
      (node (ref "U300") (pin "13") (pinfunction "EN/FAULT_13") (pintype "bidirectional"))
    )
    (net (code "49") (name "PA5{slash}SPI1_SCK") (class "Default")
      (node (ref "U100") (pin "11") (pinfunction "PA5_11") (pintype "bidirectional"))
      (node (ref "U302") (pin "2") (pinfunction "SCLK_2") (pintype "input"))
    )
    (net (code "50") (name "PA6{slash}SPI1_NSS") (class "Default")
      (node (ref "U100") (pin "12") (pinfunction "PA6_12") (pintype "bidirectional"))
      (node (ref "U302") (pin "1") (pinfunction "CSN_1") (pintype "input"))
    )
    (net (code "51") (name "PA7{slash}INUL") (class "Default")
      (node (ref "U100") (pin "13") (pinfunction "PA7_13") (pintype "bidirectional"))
      (node (ref "U300") (pin "1") (pinfunction "INUL_1") (pintype "input"))
    )
    (net (code "52") (name "PA8{slash}INUH{slash}PWM_MAG") (class "Default")
      (node (ref "R406") (pin "2") (pinfunction "2_2") (pintype "passive"))
      (node (ref "U100") (pin "18") (pinfunction "PA8_18") (pintype "bidirectional"))
      (node (ref "U300") (pin "2") (pinfunction "INUH_2") (pintype "input"))
    )
    (net (code "53") (name "PA9{slash}INVH{slash}DIR_MAG") (class "Default")
      (node (ref "R405") (pin "2") (pinfunction "2_2") (pintype "passive"))
      (node (ref "U100") (pin "19") (pinfunction "PA9_19") (pintype "bidirectional"))
      (node (ref "U300") (pin "16") (pinfunction "INVH_16") (pintype "input"))
    )
    (net (code "54") (name "PA10{slash}INWH") (class "Default")
      (node (ref "U100") (pin "20") (pinfunction "PA10_20") (pintype "bidirectional"))
      (node (ref "U300") (pin "12") (pinfunction "INWH_12") (pintype "input"))
    )
    (net (code "55") (name "PA15{slash}CAN_SILENT") (class "Default")
      (node (ref "U100") (pin "25") (pinfunction "PA15_25") (pintype "bidirectional"))
      (node (ref "U101") (pin "8") (pinfunction "S_8") (pintype "input"))
    )
    (net (code "56") (name "PB0{slash}INVL") (class "Default")
      (node (ref "U100") (pin "14") (pinfunction "PB0_14") (pintype "bidirectional"))
      (node (ref "U300") (pin "15") (pinfunction "INVL_15") (pintype "input"))
    )
    (net (code "57") (name "PB1{slash}INWL") (class "Default")
      (node (ref "U100") (pin "15") (pinfunction "PB1_15") (pintype "bidirectional"))
      (node (ref "U300") (pin "11") (pinfunction "INWL_11") (pintype "input"))
    )
    (net (code "58") (name "PB3{slash}EN_MAG") (class "Default")
      (node (ref "R402") (pin "2") (pinfunction "2_2") (pintype "passive"))
      (node (ref "U100") (pin "26") (pinfunction "PB3_26") (pintype "bidirectional"))
    )
    (net (code "59") (name "PB4{slash}SPI1_MISO") (class "Default")
      (node (ref "U100") (pin "27") (pinfunction "PB4_27") (pintype "bidirectional"))
      (node (ref "U302") (pin "3") (pinfunction "MISO_3") (pintype "output"))
    )
    (net (code "60") (name "PB5") (class "Default")
      (node (ref "U100") (pin "28") (pinfunction "PB5_28") (pintype "bidirectional"))
    )
    (net (code "61") (name "PB6{slash}EN_BLDC") (class "Default")
      (node (ref "R302") (pin "2") (pinfunction "2_2") (pintype "passive"))
      (node (ref "U100") (pin "29") (pinfunction "PB6_29") (pintype "bidirectional"))
    )
    (net (code "62") (name "PB7{slash}FAULT_MAG") (class "Default")
      (node (ref "C405") (pin "2") (pinfunction "2_2") (pintype "passive"))
      (node (ref "R402") (pin "1") (pinfunction "1_1") (pintype "passive"))
      (node (ref "U100") (pin "30") (pinfunction "PB7_30") (pintype "bidirectional"))
      (node (ref "U400") (pin "13") (pinfunction "EN/FAULT_13") (pintype "bidirectional"))
    )
    (net (code "63") (name "STBY{slash}RESET_BLDC") (class "Default")
      (node (ref "TP2") (pin "TP") (pinfunction "TP_TP") (pintype "input"))
      (node (ref "U300") (pin "14") (pinfunction "STBY/RESET_14") (pintype "input"))
    )
    (net (code "64") (name "STBY{slash}RESET_MAG") (class "Default")
      (node (ref "TP3") (pin "TP") (pinfunction "TP_TP") (pintype "input"))
      (node (ref "U400") (pin "14") (pinfunction "STBY/RESET_14") (pintype "bidirectional"))
    )
    (net (code "65") (name "SWCLK") (class "Default")
      (node (ref "J1") (pin "SWDCLK") (pinfunction "SWDCLK/TCK_SWDCLK") (pintype "passive"))
      (node (ref "U100") (pin "24") (pinfunction "PA14-SWCLK_24") (pintype "bidirectional"))
    )
    (net (code "66") (name "SWDIO") (class "Default")
      (node (ref "J1") (pin "SWDIO") (pinfunction "SWDIO/TMS_SWDIO") (pintype "passive"))
      (node (ref "U100") (pin "23") (pinfunction "PA13-SWDIO_23") (pintype "bidirectional"))
    )
    (net (code "67") (name "V_BATT") (class "Default")
      (node (ref "JP1") (pin "1") (pinfunction "1_1") (pintype "passive"))
      (node (ref "JP103") (pin "P$4") (pinfunction "VCC_P$4") (pintype "passive"))
      (node (ref "R201") (pin "2") (pinfunction "2_2") (pintype "passive"))
      (node (ref "R303") (pin "2") (pinfunction "2_2") (pintype "passive"))
      (node (ref "R403") (pin "2") (pinfunction "2_2") (pintype "passive"))
    )
    (net (code "68") (name "unconnected-(J1-NC{slash}TDI-PadNC)") (class "Default")
      (node (ref "J1") (pin "NC") (pinfunction "NC/TDI_NC") (pintype "passive"))
    )
    (net (code "69") (name "unconnected-(J1-PadGNDDET)") (class "Default")
      (node (ref "J1") (pin "GNDDET") (pinfunction "GNDDET_GNDDET") (pintype "passive"))
    )
    (net (code "70") (name "unconnected-(J1-SWO{slash}TDO-PadSWO)") (class "Default")
      (node (ref "J1") (pin "SWO") (pinfunction "SWO/TDO_SWO") (pintype "passive"))
    )
    (net (code "71") (name "unconnected-(JP103-CTS-PadP$5)") (class "Default")
      (node (ref "JP103") (pin "P$5") (pinfunction "CTS_P$5") (pintype "passive"))
    )
    (net (code "72") (name "unconnected-(JP103-DTR-PadP$1)") (class "Default")
      (node (ref "JP103") (pin "P$1") (pinfunction "DTR_P$1") (pintype "passive"))
    )
    (net (code "73") (name "unconnected-(U302-I{slash}PWM-Pad14)") (class "Default")
      (node (ref "U302") (pin "14") (pinfunction "I/PWM_14") (pintype "output"))
    )
    (net (code "74") (name "unconnected-(U302-U-Pad10)") (class "Default")
      (node (ref "U302") (pin "10") (pinfunction "U_10") (pintype "output"))
    )
    (net (code "75") (name "unconnected-(U302-V-Pad9)") (class "Default")
      (node (ref "U302") (pin "9") (pinfunction "V_9") (pintype "output"))
    )
    (net (code "76") (name "unconnected-(U302-W{slash}PWM-Pad8)") (class "Default")
      (node (ref "U302") (pin "8") (pinfunction "W/PWM_8") (pintype "output"))
    )
  )
)
